# Angin_Arus.net
KiCad netlist of a schematic drawn in EAGLE
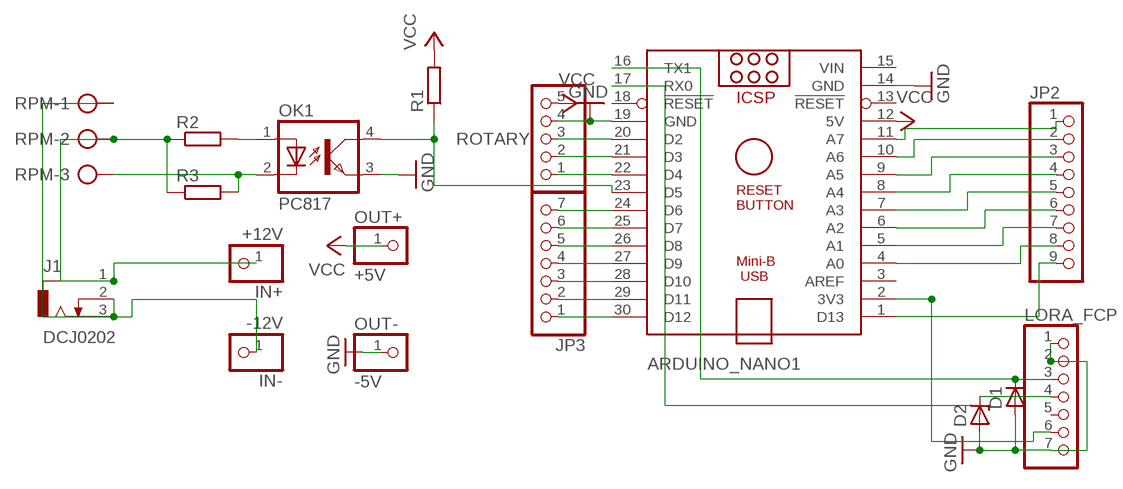
[diagram p0: schematic, sheet 1]

(export (version "E")
  (design (tool "Eeschema 10.0.6"))
  (components
    (comp (ref "ARDUINO_NANO1")
      (value "ARDUINO_NANO")
      (footprint "eagle-import:ARDUINO_NANO")
      (libsource (lib "eagle-import") (part "ARDUINO_NANO"))
    )
    (comp (ref "D1")
      (value "ZENER-DIODEDO35Z10")
      (footprint "eagle-import:DO35Z10")
      (libsource (lib "eagle-import") (part "ZENER-DIODEDO35Z10"))
    )
    (comp (ref "D2")
      (value "ZENER-DIODEDO35Z10")
      (footprint "eagle-import:DO35Z10")
      (libsource (lib "eagle-import") (part "ZENER-DIODEDO35Z10"))
    )
    (comp (ref "IN+")
      (value "+12V")
      (footprint "eagle-import:1X01")
      (libsource (lib "eagle-import") (part "PINHD-1X1"))
    )
    (comp (ref "IN-")
      (value "-12V")
      (footprint "eagle-import:1X01")
      (libsource (lib "eagle-import") (part "PINHD-1X1"))
    )
    (comp (ref "J1")
      (value "DCJ0202")
      (footprint "eagle-import:DCJ0202")
      (libsource (lib "eagle-import") (part "DCJ0202"))
    )
    (comp (ref "JP2")
      (value "PINHD-1X9")
      (footprint "eagle-import:1X09")
      (libsource (lib "eagle-import") (part "PINHD-1X9"))
    )
    (comp (ref "JP3")
      (value "PINHD-1X7")
      (footprint "eagle-import:1X07")
      (libsource (lib "eagle-import") (part "PINHD-1X7"))
    )
    (comp (ref "LORA_FCP")
      (value "PINHD-1X7")
      (footprint "eagle-import:1X07")
      (libsource (lib "eagle-import") (part "PINHD-1X7"))
    )
    (comp (ref "OK1")
      (value "PC817")
      (footprint "eagle-import:DIL04")
      (fields (field (name "MPN") "PC817X4J000F"))
      (libsource (lib "eagle-import") (part "PC817"))
    )
    (comp (ref "OUT+")
      (value "+5V")
      (footprint "eagle-import:1X01")
      (libsource (lib "eagle-import") (part "PINHD-1X1"))
    )
    (comp (ref "OUT-")
      (value "-5V")
      (footprint "eagle-import:1X01")
      (libsource (lib "eagle-import") (part "PINHD-1X1"))
    )
    (comp (ref "R1")
      (value "R-EU_0204/7")
      (footprint "eagle-import:0204_7")
      (libsource (lib "eagle-import") (part "R-EU_0204/7"))
    )
    (comp (ref "R2")
      (value "R-EU_0204/7")
      (footprint "eagle-import:0204_7")
      (libsource (lib "eagle-import") (part "R-EU_0204/7"))
    )
    (comp (ref "R3")
      (value "R-EU_0204/7")
      (footprint "eagle-import:0204_7")
      (libsource (lib "eagle-import") (part "R-EU_0204/7"))
    )
    (comp (ref "ROTARY")
      (value "PINHD-1X5")
      (footprint "eagle-import:1X05")
      (libsource (lib "eagle-import") (part "PINHD-1X5"))
    )
    (comp (ref "RPM")
      (value "AK300/3")
      (footprint "eagle-import:AK300_3")
      (libsource (lib "eagle-import") (part "AK300/3"))
    )
  )
  (nets
    (net (code "1") (name "/VIN") (class "Default")
      (node (ref "ARDUINO_NANO1") (pin "15") (pinfunction "VIN_15") (pintype "power_in"))
    )
    (net (code "2") (name "GND") (class "Default")
      (node (ref "ARDUINO_NANO1") (pin "14") (pinfunction "GND_14") (pintype "power_in"))
      (node (ref "ARDUINO_NANO1") (pin "19") (pinfunction "GND_19") (pintype "power_in"))
      (node (ref "D1") (pin "A") (pinfunction "A_A") (pintype "passive"))
      (node (ref "D2") (pin "A") (pinfunction "A_A") (pintype "passive"))
      (node (ref "LORA_FCP") (pin "1") (pinfunction "1_1") (pintype "passive"))
      (node (ref "LORA_FCP") (pin "2") (pinfunction "2_2") (pintype "passive"))
      (node (ref "LORA_FCP") (pin "7") (pinfunction "7_7") (pintype "passive"))
      (node (ref "OK1") (pin "3") (pinfunction "EMIT_3") (pintype "passive"))
      (node (ref "OUT-") (pin "1") (pinfunction "1_1") (pintype "passive"))
      (node (ref "ROTARY") (pin "4") (pinfunction "4_4") (pintype "passive"))
    )
    (net (code "3") (name "Net-(ARDUINO_NANO1-3V3)") (class "Default")
      (node (ref "ARDUINO_NANO1") (pin "2") (pinfunction "3V3_2") (pintype "output"))
      (node (ref "LORA_FCP") (pin "6") (pinfunction "6_6") (pintype "passive"))
    )
    (net (code "4") (name "Net-(ARDUINO_NANO1-A0)") (class "Default")
      (node (ref "ARDUINO_NANO1") (pin "4") (pinfunction "A0_4") (pintype "bidirectional"))
      (node (ref "JP2") (pin "8") (pinfunction "8_8") (pintype "passive"))
    )
    (net (code "5") (name "Net-(ARDUINO_NANO1-A1)") (class "Default")
      (node (ref "ARDUINO_NANO1") (pin "5") (pinfunction "A1_5") (pintype "bidirectional"))
      (node (ref "JP2") (pin "7") (pinfunction "7_7") (pintype "passive"))
    )
    (net (code "6") (name "Net-(ARDUINO_NANO1-A2)") (class "Default")
      (node (ref "ARDUINO_NANO1") (pin "6") (pinfunction "A2_6") (pintype "bidirectional"))
      (node (ref "JP2") (pin "6") (pinfunction "6_6") (pintype "passive"))
    )
    (net (code "7") (name "Net-(ARDUINO_NANO1-A3)") (class "Default")
      (node (ref "ARDUINO_NANO1") (pin "7") (pinfunction "A3_7") (pintype "bidirectional"))
      (node (ref "JP2") (pin "5") (pinfunction "5_5") (pintype "passive"))
    )
    (net (code "8") (name "Net-(ARDUINO_NANO1-A4)") (class "Default")
      (node (ref "ARDUINO_NANO1") (pin "8") (pinfunction "A4_8") (pintype "bidirectional"))
      (node (ref "JP2") (pin "4") (pinfunction "4_4") (pintype "passive"))
    )
    (net (code "9") (name "Net-(ARDUINO_NANO1-A5)") (class "Default")
      (node (ref "ARDUINO_NANO1") (pin "9") (pinfunction "A5_9") (pintype "bidirectional"))
      (node (ref "JP2") (pin "3") (pinfunction "3_3") (pintype "passive"))
    )
    (net (code "10") (name "Net-(ARDUINO_NANO1-A6)") (class "Default")
      (node (ref "ARDUINO_NANO1") (pin "10") (pinfunction "A6_10") (pintype "bidirectional"))
      (node (ref "JP2") (pin "2") (pinfunction "2_2") (pintype "passive"))
    )
    (net (code "11") (name "Net-(ARDUINO_NANO1-A7)") (class "Default")
      (node (ref "ARDUINO_NANO1") (pin "11") (pinfunction "A7_11") (pintype "bidirectional"))
      (node (ref "JP2") (pin "1") (pinfunction "1_1") (pintype "passive"))
    )
    (net (code "12") (name "Net-(ARDUINO_NANO1-D2)") (class "Default")
      (node (ref "ARDUINO_NANO1") (pin "20") (pinfunction "D2_20") (pintype "bidirectional"))
      (node (ref "ROTARY") (pin "3") (pinfunction "3_3") (pintype "passive"))
    )
    (net (code "13") (name "Net-(ARDUINO_NANO1-D3)") (class "Default")
      (node (ref "ARDUINO_NANO1") (pin "21") (pinfunction "D3_21") (pintype "bidirectional"))
      (node (ref "ROTARY") (pin "2") (pinfunction "2_2") (pintype "passive"))
    )
    (net (code "14") (name "Net-(ARDUINO_NANO1-D4)") (class "Default")
      (node (ref "ARDUINO_NANO1") (pin "22") (pinfunction "D4_22") (pintype "bidirectional"))
      (node (ref "ROTARY") (pin "1") (pinfunction "1_1") (pintype "passive"))
    )
    (net (code "15") (name "Net-(ARDUINO_NANO1-D5)") (class "Default")
      (node (ref "ARDUINO_NANO1") (pin "23") (pinfunction "D5_23") (pintype "bidirectional"))
      (node (ref "OK1") (pin "4") (pinfunction "COL_4") (pintype "passive"))
      (node (ref "R1") (pin "1") (pinfunction "1_1") (pintype "passive"))
    )
    (net (code "16") (name "Net-(ARDUINO_NANO1-D6)") (class "Default")
      (node (ref "ARDUINO_NANO1") (pin "24") (pinfunction "D6_24") (pintype "bidirectional"))
      (node (ref "JP3") (pin "7") (pinfunction "7_7") (pintype "passive"))
    )
    (net (code "17") (name "Net-(ARDUINO_NANO1-D7)") (class "Default")
      (node (ref "ARDUINO_NANO1") (pin "25") (pinfunction "D7_25") (pintype "bidirectional"))
      (node (ref "JP3") (pin "6") (pinfunction "6_6") (pintype "passive"))
    )
    (net (code "18") (name "Net-(ARDUINO_NANO1-D8)") (class "Default")
      (node (ref "ARDUINO_NANO1") (pin "26") (pinfunction "D8_26") (pintype "bidirectional"))
      (node (ref "JP3") (pin "5") (pinfunction "5_5") (pintype "passive"))
    )
    (net (code "19") (name "Net-(ARDUINO_NANO1-D9)") (class "Default")
      (node (ref "ARDUINO_NANO1") (pin "27") (pinfunction "D9_27") (pintype "bidirectional"))
      (node (ref "JP3") (pin "4") (pinfunction "4_4") (pintype "passive"))
    )
    (net (code "20") (name "Net-(ARDUINO_NANO1-D10)") (class "Default")
      (node (ref "ARDUINO_NANO1") (pin "28") (pinfunction "D10_28") (pintype "bidirectional"))
      (node (ref "JP3") (pin "3") (pinfunction "3_3") (pintype "passive"))
    )
    (net (code "21") (name "Net-(ARDUINO_NANO1-D11)") (class "Default")
      (node (ref "ARDUINO_NANO1") (pin "29") (pinfunction "D11_29") (pintype "bidirectional"))
      (node (ref "JP3") (pin "2") (pinfunction "2_2") (pintype "passive"))
    )
    (net (code "22") (name "Net-(ARDUINO_NANO1-D12)") (class "Default")
      (node (ref "ARDUINO_NANO1") (pin "30") (pinfunction "D12_30") (pintype "bidirectional"))
      (node (ref "JP3") (pin "1") (pinfunction "1_1") (pintype "passive"))
    )
    (net (code "23") (name "Net-(ARDUINO_NANO1-D13)") (class "Default")
      (node (ref "ARDUINO_NANO1") (pin "1") (pinfunction "D13_1") (pintype "bidirectional"))
      (node (ref "JP2") (pin "9") (pinfunction "9_9") (pintype "passive"))
    )
    (net (code "24") (name "Net-(ARDUINO_NANO1-TX1)") (class "Default")
      (node (ref "ARDUINO_NANO1") (pin "16") (pinfunction "TX1_16") (pintype "bidirectional"))
      (node (ref "D1") (pin "C") (pinfunction "C_C") (pintype "passive"))
      (node (ref "LORA_FCP") (pin "3") (pinfunction "3_3") (pintype "passive"))
    )
    (net (code "25") (name "Net-(D2-PadC)") (class "Default")
      (node (ref "D2") (pin "C") (pinfunction "C_C") (pintype "passive"))
      (node (ref "LORA_FCP") (pin "4") (pinfunction "4_4") (pintype "passive"))
    )
    (net (code "26") (name "Net-(OK1-A)") (class "Default")
      (node (ref "OK1") (pin "1") (pinfunction "A_1") (pintype "passive"))
      (node (ref "R2") (pin "2") (pinfunction "2_2") (pintype "passive"))
    )
    (net (code "27") (name "Net-(OK1-C)") (class "Default")
      (node (ref "OK1") (pin "2") (pinfunction "C_2") (pintype "passive"))
      (node (ref "R3") (pin "2") (pinfunction "2_2") (pintype "passive"))
      (node (ref "RPM") (pin "3") (pinfunction "KL_3") (pintype "passive"))
    )
    (net (code "28") (name "Net-(RPMA-KL)") (class "Default")
      (node (ref "IN-") (pin "1") (pinfunction "1_1") (pintype "passive"))
      (node (ref "J1") (pin "2") (pinfunction "2_2") (pintype "passive"))
      (node (ref "J1") (pin "3") (pinfunction "3_3") (pintype "passive"))
      (node (ref "RPM") (pin "1") (pinfunction "KL_1") (pintype "passive"))
    )
    (net (code "29") (name "Net-(RPMB-KL)") (class "Default")
      (node (ref "IN+") (pin "1") (pinfunction "1_1") (pintype "passive"))
      (node (ref "J1") (pin "1") (pinfunction "1_1") (pintype "passive"))
      (node (ref "R2") (pin "1") (pinfunction "1_1") (pintype "passive"))
      (node (ref "R3") (pin "1") (pinfunction "1_1") (pintype "passive"))
      (node (ref "RPM") (pin "2") (pinfunction "KL_2") (pintype "passive"))
    )
    (net (code "30") (name "VCC") (class "Default")
      (node (ref "ARDUINO_NANO1") (pin "12") (pinfunction "5V_12") (pintype "power_in"))
      (node (ref "OUT+") (pin "1") (pinfunction "1_1") (pintype "passive"))
      (node (ref "R1") (pin "2") (pinfunction "2_2") (pintype "passive"))
      (node (ref "ROTARY") (pin "5") (pinfunction "5_5") (pintype "passive"))
    )
    (net (code "31") (name "unconnected-(ARDUINO_NANO1-AREF-Pad3)") (class "Default")
      (node (ref "ARDUINO_NANO1") (pin "3") (pinfunction "AREF_3") (pintype "input"))
    )
    (net (code "32") (name "unconnected-(ARDUINO_NANO1-RX0-Pad17)") (class "Default")
      (node (ref "ARDUINO_NANO1") (pin "17") (pinfunction "RX0_17") (pintype "bidirectional"))
    )
    (net (code "33") (name "unconnected-(ARDUINO_NANO1-~{RESET}-Pad13)") (class "Default")
      (node (ref "ARDUINO_NANO1") (pin "13") (pinfunction "~{RESET}_13") (pintype "input"))
    )
    (net (code "34") (name "unconnected-(ARDUINO_NANO1-~{RESET}-Pad18)") (class "Default")
      (node (ref "ARDUINO_NANO1") (pin "18") (pinfunction "~{RESET}_18") (pintype "input"))
    )
    (net (code "35") (name "unconnected-(LORA_FCP-Pad5)") (class "Default")
      (node (ref "LORA_FCP") (pin "5") (pinfunction "5_5") (pintype "passive"))
    )
  )
)
